# Pugsley.net
KiCad netlist of a schematic drawn in EAGLE
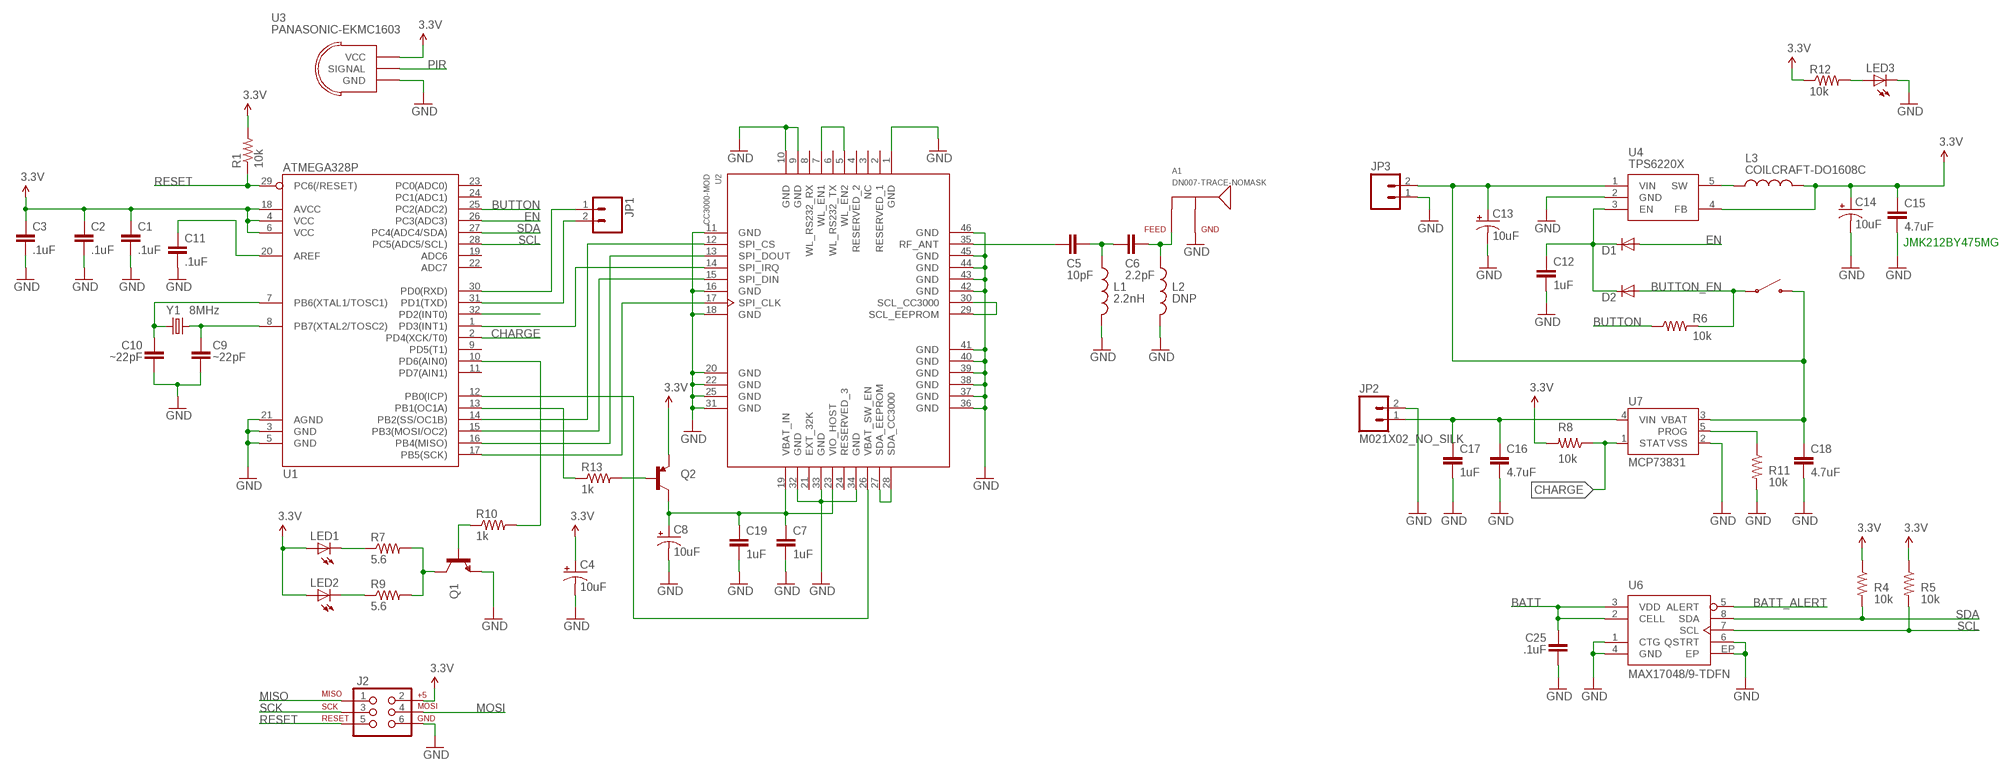
[diagram p0: schematic, sheet 1]

(export (version "E")
  (design (tool "Eeschema 10.0.6"))
  (components
    (comp (ref "A1")
      (value "DN007-TRACE-NOMASK")
      (footprint "eagle-import:DN007-TRACE-NOMASK")
      (libsource (lib "eagle-import") (part "DN007-TRACE-NOMASK"))
    )
    (comp (ref "C1")
      (value ".1uF")
      (footprint "eagle-import:0402-CAP")
      (libsource (lib "eagle-import") (part "CAP0402-CAP"))
    )
    (comp (ref "C2")
      (value ".1uF")
      (footprint "eagle-import:0402-CAP")
      (libsource (lib "eagle-import") (part "CAP0402-CAP"))
    )
    (comp (ref "C3")
      (value ".1uF")
      (footprint "eagle-import:0402-CAP")
      (libsource (lib "eagle-import") (part "CAP0402-CAP"))
    )
    (comp (ref "C4")
      (value "10uF")
      (footprint "eagle-import:EIA3216")
      (libsource (lib "eagle-import") (part "CAP_POL1206"))
    )
    (comp (ref "C5")
      (value "10pF")
      (footprint "eagle-import:0402-CAP")
      (libsource (lib "eagle-import") (part "CAP0402-CAP"))
    )
    (comp (ref "C6")
      (value "2.2pF")
      (footprint "eagle-import:0402-CAP")
      (libsource (lib "eagle-import") (part "CAP0402-CAP"))
    )
    (comp (ref "C7")
      (value "1uF")
      (footprint "eagle-import:0402-CAP")
      (libsource (lib "eagle-import") (part "CAP0402-CAP"))
    )
    (comp (ref "C8")
      (value "10uF")
      (footprint "eagle-import:EIA3216")
      (libsource (lib "eagle-import") (part "CAP_POL1206"))
    )
    (comp (ref "C9")
      (value "~22pF")
      (footprint "eagle-import:0402-CAP")
      (libsource (lib "eagle-import") (part "CAP0402-CAP"))
    )
    (comp (ref "C10")
      (value "~22pF")
      (footprint "eagle-import:0402-CAP")
      (libsource (lib "eagle-import") (part "CAP0402-CAP"))
    )
    (comp (ref "C11")
      (value ".1uF")
      (footprint "eagle-import:0402-CAP")
      (libsource (lib "eagle-import") (part "CAP0402-CAP"))
    )
    (comp (ref "C12")
      (value "1uF")
      (footprint "eagle-import:0402-CAP")
      (libsource (lib "eagle-import") (part "CAP0402-CAP"))
    )
    (comp (ref "C13")
      (value "10uF")
      (footprint "eagle-import:EIA3216")
      (libsource (lib "eagle-import") (part "CAP_POL1206"))
    )
    (comp (ref "C14")
      (value "10uF")
      (footprint "eagle-import:EIA3216")
      (libsource (lib "eagle-import") (part "CAP_POL1206"))
    )
    (comp (ref "C15")
      (value "4.7uF")
      (footprint "eagle-import:0805")
      (libsource (lib "eagle-import") (part "CAP0805"))
    )
    (comp (ref "C16")
      (value "4.7uF")
      (footprint "eagle-import:0805")
      (libsource (lib "eagle-import") (part "CAP0805"))
    )
    (comp (ref "C17")
      (value "1uF")
      (footprint "eagle-import:0402-CAP")
      (libsource (lib "eagle-import") (part "CAP0402-CAP"))
    )
    (comp (ref "C18")
      (value "4.7uF")
      (footprint "eagle-import:0805")
      (libsource (lib "eagle-import") (part "CAP0805"))
    )
    (comp (ref "C19")
      (value "1uF")
      (footprint "eagle-import:0402-CAP")
      (libsource (lib "eagle-import") (part "CAP0402-CAP"))
    )
    (comp (ref "C25")
      (value ".1uF")
      (footprint "eagle-import:0402-CAP")
      (libsource (lib "eagle-import") (part "CAP0402-CAP"))
    )
    (comp (ref "D1")
      (value "DIODESOD")
      (footprint "eagle-import:SOD-323")
      (libsource (lib "eagle-import") (part "DIODESOD"))
    )
    (comp (ref "D2")
      (value "DIODESOD")
      (footprint "eagle-import:SOD-323")
      (libsource (lib "eagle-import") (part "DIODESOD"))
    )
    (comp (ref "J2")
      (value "AVR_SPI_PRG_6NS")
      (footprint "eagle-import:2X3-NS")
      (libsource (lib "eagle-import") (part "AVR_SPI_PRG_6NS"))
    )
    (comp (ref "JP1")
      (value "M021X02_NO_SILK")
      (footprint "eagle-import:1X02_NO_SILK")
      (libsource (lib "eagle-import") (part "M021X02_NO_SILK"))
    )
    (comp (ref "JP2")
      (value "M021X02_NO_SILK")
      (footprint "eagle-import:1X02_NO_SILK")
      (libsource (lib "eagle-import") (part "M021X02_NO_SILK"))
    )
    (comp (ref "JP3")
      (value "M021X02_NO_SILK")
      (footprint "eagle-import:1X02_NO_SILK")
      (libsource (lib "eagle-import") (part "M021X02_NO_SILK"))
    )
    (comp (ref "L1")
      (value "2.2nH")
      (footprint "eagle-import:C0402")
      (libsource (lib "eagle-import") (part "INDUCTOR0402"))
    )
    (comp (ref "L2")
      (value "DNP")
      (footprint "eagle-import:C0402")
      (libsource (lib "eagle-import") (part "INDUCTOR0402"))
    )
    (comp (ref "L3")
      (value "COILCRAFT-DO1608C")
      (footprint "eagle-import:COILCRAFT-DO1608C")
      (libsource (lib "eagle-import") (part "COILCRAFT-DO1608C"))
    )
    (comp (ref "LED1")
      (value "LED0603")
      (footprint "eagle-import:LED-0603")
      (libsource (lib "eagle-import") (part "LED0603"))
    )
    (comp (ref "LED2")
      (value "LED0603")
      (footprint "eagle-import:LED-0603")
      (libsource (lib "eagle-import") (part "LED0603"))
    )
    (comp (ref "LED3")
      (value "LED0603")
      (footprint "eagle-import:LED-0603")
      (libsource (lib "eagle-import") (part "LED0603"))
    )
    (comp (ref "Q1")
      (value "TRANSISTOR_NPNSOT23")
      (footprint "eagle-import:SOT23")
      (libsource (lib "eagle-import") (part "TRANSISTOR_NPNSOT23"))
    )
    (comp (ref "Q2")
      (value "TRANSISTOR_PNPSMD")
      (footprint "eagle-import:SOT23-3")
      (libsource (lib "eagle-import") (part "TRANSISTOR_PNPSMD"))
    )
    (comp (ref "R1")
      (value "10k")
      (footprint "eagle-import:0402-RES")
      (libsource (lib "eagle-import") (part "RESISTOR0402-RES"))
    )
    (comp (ref "R4")
      (value "10k")
      (footprint "eagle-import:0402-RES")
      (libsource (lib "eagle-import") (part "RESISTOR0402-RES"))
    )
    (comp (ref "R5")
      (value "10k")
      (footprint "eagle-import:0402-RES")
      (libsource (lib "eagle-import") (part "RESISTOR0402-RES"))
    )
    (comp (ref "R6")
      (value "10k")
      (footprint "eagle-import:0402-RES")
      (libsource (lib "eagle-import") (part "RESISTOR0402-RES"))
    )
    (comp (ref "R7")
      (value "5.6")
      (footprint "eagle-import:0402-RES")
      (libsource (lib "eagle-import") (part "RESISTOR0402-RES"))
    )
    (comp (ref "R8")
      (value "10k")
      (footprint "eagle-import:0402-RES")
      (libsource (lib "eagle-import") (part "RESISTOR0402-RES"))
    )
    (comp (ref "R9")
      (value "5.6")
      (footprint "eagle-import:0402-RES")
      (libsource (lib "eagle-import") (part "RESISTOR0402-RES"))
    )
    (comp (ref "R10")
      (value "1k")
      (footprint "eagle-import:0402-RES")
      (libsource (lib "eagle-import") (part "RESISTOR0402-RES"))
    )
    (comp (ref "R11")
      (value "10k")
      (footprint "eagle-import:0402-RES")
      (libsource (lib "eagle-import") (part "RESISTOR0402-RES"))
    )
    (comp (ref "R12")
      (value "10k")
      (footprint "eagle-import:0402-RES")
      (libsource (lib "eagle-import") (part "RESISTOR0402-RES"))
    )
    (comp (ref "R13")
      (value "1k")
      (footprint "eagle-import:0402-RES")
      (libsource (lib "eagle-import") (part "RESISTOR0402-RES"))
    )
    (comp (ref "S1")
      (value "C&K-KSR2XX")
      (footprint "eagle-import:C&K-KSR2XX")
      (libsource (lib "eagle-import") (part "C&K-KSR2XX"))
    )
    (comp (ref "U1")
      (value "ATMEGA328P")
      (footprint "eagle-import:TQFP32-08")
      (libsource (lib "eagle-import") (part "ATMEGA328_SMT"))
    )
    (comp (ref "U2")
      (value "CC3000-MOD")
      (footprint "eagle-import:CC3000")
      (libsource (lib "eagle-import") (part "CC3000-MOD"))
    )
    (comp (ref "U3")
      (value "PANASONIC-EKMC1603")
      (footprint "eagle-import:PIR-PANASONIC-EKMC1603XXX")
      (libsource (lib "eagle-import") (part "PANASONIC-EKMC1603"))
    )
    (comp (ref "U4")
      (value "TPS6220X")
      (footprint "eagle-import:SOT23-5")
      (libsource (lib "eagle-import") (part "TPS6220X"))
    )
    (comp (ref "U6")
      (value "MAX17048/9-TDFN")
      (footprint "eagle-import:TDFN-8")
      (libsource (lib "eagle-import") (part "MAX17048/9-TDFN"))
    )
    (comp (ref "U7")
      (value "MCP73831")
      (footprint "eagle-import:SOT23-5")
      (libsource (lib "eagle-import") (part "MCP73831"))
    )
    (comp (ref "Y1")
      (value "8MHz")
      (footprint "eagle-import:CRYSTAL-SMD-5X3")
      (libsource (lib "eagle-import") (part "CRYSTAL5X3"))
    )
  )
  (nets
    (net (code "1") (name "/BATT") (class "Default")
      (node (ref "C13") (pin "A") (pinfunction "+_A") (pintype "passive"))
      (node (ref "C18") (pin "1") (pinfunction "1_1") (pintype "passive"))
      (node (ref "C25") (pin "1") (pinfunction "1_1") (pintype "passive"))
      (node (ref "JP3") (pin "2") (pinfunction "2_2") (pintype "passive"))
      (node (ref "S1") (pin "P$2") (pinfunction "2_P$2") (pintype "bidirectional"))
      (node (ref "U4") (pin "1") (pinfunction "VIN_1") (pintype "power_in"))
      (node (ref "U6") (pin "2") (pinfunction "CELL_2") (pintype "input"))
      (node (ref "U6") (pin "3") (pinfunction "VDD_3") (pintype "power_in"))
      (node (ref "U7") (pin "3") (pinfunction "VBAT_3") (pintype "power_in"))
    )
    (net (code "2") (name "/BATT_ALERT") (class "Default")
      (node (ref "U6") (pin "5") (pinfunction "ALERT_5") (pintype "open_collector"))
    )
    (net (code "3") (name "/BUTTON") (class "Default")
      (node (ref "R6") (pin "1") (pinfunction "1_1") (pintype "passive"))
      (node (ref "U1") (pin "25") (pinfunction "PC2(ADC2)_25") (pintype "bidirectional"))
    )
    (net (code "4") (name "/BUTTON_EN") (class "Default")
      (node (ref "D2") (pin "2") (pinfunction "A_2") (pintype "passive"))
      (node (ref "R6") (pin "2") (pinfunction "2_2") (pintype "passive"))
      (node (ref "S1") (pin "P$1") (pinfunction "1_P$1") (pintype "bidirectional"))
    )
    (net (code "5") (name "/EN") (class "Default")
      (node (ref "D1") (pin "2") (pinfunction "A_2") (pintype "passive"))
      (node (ref "U1") (pin "26") (pinfunction "PC3(ADC3)_26") (pintype "bidirectional"))
    )
    (net (code "6") (name "/MISO") (class "Default")
      (node (ref "J2") (pin "1") (pinfunction "1_1") (pintype "passive"))
      (node (ref "U1") (pin "16") (pinfunction "PB4(MISO)_16") (pintype "bidirectional"))
      (node (ref "U2") (pin "13") (pinfunction "SPI_DOUT_13") (pintype "output"))
    )
    (net (code "7") (name "/MOSI") (class "Default")
      (node (ref "J2") (pin "4") (pinfunction "4_4") (pintype "passive"))
      (node (ref "U1") (pin "15") (pinfunction "PB3(MOSI/OC2)_15") (pintype "bidirectional"))
      (node (ref "U2") (pin "15") (pinfunction "SPI_DIN_15") (pintype "input"))
    )
    (net (code "8") (name "/PIR") (class "Default")
      (node (ref "U1") (pin "32") (pinfunction "PD2(INT0)_32") (pintype "bidirectional"))
      (node (ref "U3") (pin "OUT") (pinfunction "SIGNAL_OUT") (pintype "output"))
    )
    (net (code "9") (name "/RESET") (class "Default")
      (node (ref "J2") (pin "5") (pinfunction "5_5") (pintype "passive"))
      (node (ref "R1") (pin "1") (pinfunction "1_1") (pintype "passive"))
      (node (ref "U1") (pin "29") (pinfunction "PC6(/RESET)_29") (pintype "bidirectional"))
    )
    (net (code "10") (name "/SCK") (class "Default")
      (node (ref "J2") (pin "3") (pinfunction "3_3") (pintype "passive"))
      (node (ref "U1") (pin "17") (pinfunction "PB5(SCK)_17") (pintype "bidirectional"))
      (node (ref "U2") (pin "17") (pinfunction "SPI_CLK_17") (pintype "input"))
    )
    (net (code "11") (name "/SCL") (class "Default")
      (node (ref "R5") (pin "2") (pinfunction "2_2") (pintype "passive"))
      (node (ref "U1") (pin "28") (pinfunction "PC5(ADC5/SCL)_28") (pintype "bidirectional"))
      (node (ref "U6") (pin "7") (pinfunction "SCL_7") (pintype "input"))
    )
    (net (code "12") (name "/SDA") (class "Default")
      (node (ref "R4") (pin "2") (pinfunction "2_2") (pintype "passive"))
      (node (ref "U1") (pin "27") (pinfunction "PC4(ADC4/SDA)_27") (pintype "bidirectional"))
      (node (ref "U6") (pin "8") (pinfunction "SDA_8") (pintype "bidirectional"))
    )
    (net (code "13") (name "3.3V") (class "Default")
      (node (ref "C1") (pin "1") (pinfunction "1_1") (pintype "passive"))
      (node (ref "C14") (pin "A") (pinfunction "+_A") (pintype "passive"))
      (node (ref "C15") (pin "1") (pinfunction "1_1") (pintype "passive"))
      (node (ref "C2") (pin "1") (pinfunction "1_1") (pintype "passive"))
      (node (ref "C3") (pin "1") (pinfunction "1_1") (pintype "passive"))
      (node (ref "C4") (pin "A") (pinfunction "+_A") (pintype "passive"))
      (node (ref "J2") (pin "2") (pinfunction "2_2") (pintype "passive"))
      (node (ref "L3") (pin "2") (pinfunction "2_2") (pintype "passive"))
      (node (ref "LED1") (pin "A") (pinfunction "A_A") (pintype "passive"))
      (node (ref "LED2") (pin "A") (pinfunction "A_A") (pintype "passive"))
      (node (ref "Q2") (pin "2") (pinfunction "E_2") (pintype "passive"))
      (node (ref "R1") (pin "2") (pinfunction "2_2") (pintype "passive"))
      (node (ref "R12") (pin "1") (pinfunction "1_1") (pintype "passive"))
      (node (ref "R4") (pin "1") (pinfunction "1_1") (pintype "passive"))
      (node (ref "R5") (pin "1") (pinfunction "1_1") (pintype "passive"))
      (node (ref "R8") (pin "2") (pinfunction "2_2") (pintype "passive"))
      (node (ref "U1") (pin "18") (pinfunction "AVCC_18") (pintype "bidirectional"))
      (node (ref "U1") (pin "4") (pinfunction "VCC_4") (pintype "bidirectional"))
      (node (ref "U1") (pin "6") (pinfunction "VCC_6") (pintype "bidirectional"))
      (node (ref "U3") (pin "VDD") (pinfunction "VCC_VDD") (pintype "power_in"))
      (node (ref "U4") (pin "4") (pinfunction "FB_4") (pintype "input"))
    )
    (net (code "14") (name "CHARGE") (class "Default")
      (node (ref "R8") (pin "1") (pinfunction "1_1") (pintype "passive"))
      (node (ref "U1") (pin "2") (pinfunction "PD4(XCK/T0)_2") (pintype "bidirectional"))
      (node (ref "U7") (pin "1") (pinfunction "STAT_1") (pintype "output"))
    )
    (net (code "15") (name "GND") (class "Default")
      (node (ref "A1") (pin "GND@1") (pinfunction "GND_GND@1") (pintype "input"))
      (node (ref "A1") (pin "GND@2") (pinfunction "GND_GND@2") (pintype "input"))
      (node (ref "C1") (pin "2") (pinfunction "2_2") (pintype "passive"))
      (node (ref "C10") (pin "2") (pinfunction "2_2") (pintype "passive"))
      (node (ref "C11") (pin "2") (pinfunction "2_2") (pintype "passive"))
      (node (ref "C12") (pin "2") (pinfunction "2_2") (pintype "passive"))
      (node (ref "C13") (pin "C") (pinfunction "-_C") (pintype "passive"))
      (node (ref "C14") (pin "C") (pinfunction "-_C") (pintype "passive"))
      (node (ref "C15") (pin "2") (pinfunction "2_2") (pintype "passive"))
      (node (ref "C16") (pin "2") (pinfunction "2_2") (pintype "passive"))
      (node (ref "C17") (pin "2") (pinfunction "2_2") (pintype "passive"))
      (node (ref "C18") (pin "2") (pinfunction "2_2") (pintype "passive"))
      (node (ref "C19") (pin "2") (pinfunction "2_2") (pintype "passive"))
      (node (ref "C2") (pin "2") (pinfunction "2_2") (pintype "passive"))
      (node (ref "C25") (pin "2") (pinfunction "2_2") (pintype "passive"))
      (node (ref "C3") (pin "2") (pinfunction "2_2") (pintype "passive"))
      (node (ref "C4") (pin "C") (pinfunction "-_C") (pintype "passive"))
      (node (ref "C7") (pin "2") (pinfunction "2_2") (pintype "passive"))
      (node (ref "C8") (pin "C") (pinfunction "-_C") (pintype "passive"))
      (node (ref "C9") (pin "2") (pinfunction "2_2") (pintype "passive"))
      (node (ref "J2") (pin "6") (pinfunction "6_6") (pintype "passive"))
      (node (ref "JP2") (pin "2") (pinfunction "2_2") (pintype "passive"))
      (node (ref "JP3") (pin "1") (pinfunction "1_1") (pintype "passive"))
      (node (ref "L1") (pin "2") (pinfunction "2_2") (pintype "passive"))
      (node (ref "L2") (pin "2") (pinfunction "2_2") (pintype "passive"))
      (node (ref "LED3") (pin "C") (pinfunction "C_C") (pintype "passive"))
      (node (ref "Q1") (pin "2") (pinfunction "E_2") (pintype "passive"))
      (node (ref "R11") (pin "2") (pinfunction "2_2") (pintype "passive"))
      (node (ref "U1") (pin "21") (pinfunction "AGND_21") (pintype "bidirectional"))
      (node (ref "U1") (pin "3") (pinfunction "GND_3") (pintype "bidirectional"))
      (node (ref "U1") (pin "5") (pinfunction "GND_5") (pintype "bidirectional"))
      (node (ref "U2") (pin "1") (pinfunction "GND_1") (pintype "power_in"))
      (node (ref "U2") (pin "10") (pinfunction "GND_10") (pintype "power_in"))
      (node (ref "U2") (pin "11") (pinfunction "GND_11") (pintype "power_in"))
      (node (ref "U2") (pin "16") (pinfunction "GND_16") (pintype "power_in"))
      (node (ref "U2") (pin "18") (pinfunction "GND_18") (pintype "power_in"))
      (node (ref "U2") (pin "20") (pinfunction "GND_20") (pintype "power_in"))
      (node (ref "U2") (pin "22") (pinfunction "GND_22") (pintype "power_in"))
      (node (ref "U2") (pin "25") (pinfunction "GND_25") (pintype "power_in"))
      (node (ref "U2") (pin "31") (pinfunction "GND_31") (pintype "power_in"))
      (node (ref "U2") (pin "32") (pinfunction "GND_32") (pintype "power_in"))
      (node (ref "U2") (pin "33") (pinfunction "GND_33") (pintype "power_in"))
      (node (ref "U2") (pin "34") (pinfunction "GND_34") (pintype "power_in"))
      (node (ref "U2") (pin "36") (pinfunction "GND_36") (pintype "power_in"))
      (node (ref "U2") (pin "37") (pinfunction "GND_37") (pintype "power_in"))
      (node (ref "U2") (pin "38") (pinfunction "GND_38") (pintype "power_in"))
      (node (ref "U2") (pin "39") (pinfunction "GND_39") (pintype "power_in"))
      (node (ref "U2") (pin "40") (pinfunction "GND_40") (pintype "power_in"))
      (node (ref "U2") (pin "41") (pinfunction "GND_41") (pintype "power_in"))
      (node (ref "U2") (pin "42") (pinfunction "GND_42") (pintype "power_in"))
      (node (ref "U2") (pin "43") (pinfunction "GND_43") (pintype "power_in"))
      (node (ref "U2") (pin "44") (pinfunction "GND_44") (pintype "power_in"))
      (node (ref "U2") (pin "45") (pinfunction "GND_45") (pintype "power_in"))
      (node (ref "U2") (pin "46") (pinfunction "GND_46") (pintype "power_in"))
      (node (ref "U2") (pin "9") (pinfunction "GND_9") (pintype "power_in"))
      (node (ref "U3") (pin "GND") (pinfunction "GND_GND") (pintype "power_in"))
      (node (ref "U4") (pin "2") (pinfunction "GND_2") (pintype "power_in"))
      (node (ref "U6") (pin "1") (pinfunction "CTG_1") (pintype "power_in"))
      (node (ref "U6") (pin "4") (pinfunction "GND_4") (pintype "power_in"))
      (node (ref "U6") (pin "6") (pinfunction "QSTRT_6") (pintype "input"))
      (node (ref "U6") (pin "EP") (pinfunction "EP_EP") (pintype "power_in"))
      (node (ref "U7") (pin "2") (pinfunction "VSS_2") (pintype "power_in"))
    )
    (net (code "16") (name "Net-(A1-PadFEED)") (class "Default")
      (node (ref "A1") (pin "FEED") (pinfunction "FEED_FEED") (pintype "power_in"))
      (node (ref "C6") (pin "1") (pinfunction "1_1") (pintype "passive"))
      (node (ref "L2") (pin "1") (pinfunction "1_1") (pintype "passive"))
    )
    (net (code "17") (name "Net-(C5-Pad1)") (class "Default")
      (node (ref "C5") (pin "1") (pinfunction "1_1") (pintype "passive"))
      (node (ref "C6") (pin "2") (pinfunction "2_2") (pintype "passive"))
      (node (ref "L1") (pin "1") (pinfunction "1_1") (pintype "passive"))
    )
    (net (code "18") (name "Net-(C8-+)") (class "Default")
      (node (ref "C19") (pin "1") (pinfunction "1_1") (pintype "passive"))
      (node (ref "C7") (pin "1") (pinfunction "1_1") (pintype "passive"))
      (node (ref "C8") (pin "A") (pinfunction "+_A") (pintype "passive"))
      (node (ref "Q2") (pin "3") (pinfunction "C_3") (pintype "passive"))
      (node (ref "U2") (pin "19") (pinfunction "VBAT_IN_19") (pintype "power_in"))
      (node (ref "U2") (pin "23") (pinfunction "VIO_HOST_23") (pintype "power_in"))
    )
    (net (code "19") (name "Net-(D1-C)") (class "Default")
      (node (ref "C12") (pin "1") (pinfunction "1_1") (pintype "passive"))
      (node (ref "D1") (pin "1") (pinfunction "C_1") (pintype "passive"))
      (node (ref "D2") (pin "1") (pinfunction "C_1") (pintype "passive"))
      (node (ref "U4") (pin "3") (pinfunction "EN_3") (pintype "input"))
    )
    (net (code "20") (name "Net-(LED1-PadC)") (class "Default")
      (node (ref "LED1") (pin "C") (pinfunction "C_C") (pintype "passive"))
      (node (ref "R7") (pin "1") (pinfunction "1_1") (pintype "passive"))
    )
    (net (code "21") (name "Net-(LED2-PadC)") (class "Default")
      (node (ref "LED2") (pin "C") (pinfunction "C_C") (pintype "passive"))
      (node (ref "R9") (pin "1") (pinfunction "1_1") (pintype "passive"))
    )
    (net (code "22") (name "Net-(LED3-PadA)") (class "Default")
      (node (ref "LED3") (pin "A") (pinfunction "A_A") (pintype "passive"))
      (node (ref "R12") (pin "2") (pinfunction "2_2") (pintype "passive"))
    )
    (net (code "23") (name "Net-(Q1-B)") (class "Default")
      (node (ref "Q1") (pin "1") (pinfunction "B_1") (pintype "passive"))
      (node (ref "R10") (pin "1") (pinfunction "1_1") (pintype "passive"))
    )
    (net (code "24") (name "Net-(Q1-C)") (class "Default")
      (node (ref "Q1") (pin "3") (pinfunction "C_3") (pintype "passive"))
      (node (ref "R7") (pin "2") (pinfunction "2_2") (pintype "passive"))
      (node (ref "R9") (pin "2") (pinfunction "2_2") (pintype "passive"))
    )
    (net (code "25") (name "Net-(Q2-B)") (class "Default")
      (node (ref "Q2") (pin "1") (pinfunction "B_1") (pintype "passive"))
      (node (ref "R13") (pin "2") (pinfunction "2_2") (pintype "passive"))
    )
    (net (code "26") (name "Net-(U1-AREF)") (class "Default")
      (node (ref "C11") (pin "1") (pinfunction "1_1") (pintype "passive"))
      (node (ref "U1") (pin "20") (pinfunction "AREF_20") (pintype "bidirectional"))
    )
    (net (code "27") (name "Net-(U1-PB0(ICP))") (class "Default")
      (node (ref "U1") (pin "12") (pinfunction "PB0(ICP)_12") (pintype "bidirectional"))
      (node (ref "U2") (pin "26") (pinfunction "VBAT_SW_EN_26") (pintype "input"))
    )
    (net (code "28") (name "Net-(U1-PB1(OC1A))") (class "Default")
      (node (ref "R13") (pin "1") (pinfunction "1_1") (pintype "passive"))
      (node (ref "U1") (pin "13") (pinfunction "PB1(OC1A)_13") (pintype "bidirectional"))
    )
    (net (code "29") (name "Net-(U1-PB2(SS{slash}OC1B))") (class "Default")
      (node (ref "U1") (pin "14") (pinfunction "PB2(SS/OC1B)_14") (pintype "bidirectional"))
      (node (ref "U2") (pin "12") (pinfunction "SPI_CS_12") (pintype "input"))
    )
    (net (code "30") (name "Net-(U1-PB6(XTAL1{slash}TOSC1))") (class "Default")
      (node (ref "C10") (pin "1") (pinfunction "1_1") (pintype "passive"))
      (node (ref "U1") (pin "7") (pinfunction "PB6(XTAL1/TOSC1)_7") (pintype "bidirectional"))
      (node (ref "Y1") (pin "1") (pinfunction "1_1") (pintype "passive"))
    )
    (net (code "31") (name "Net-(U1-PB7(XTAL2{slash}TOSC2))") (class "Default")
      (node (ref "C9") (pin "1") (pinfunction "1_1") (pintype "passive"))
      (node (ref "U1") (pin "8") (pinfunction "PB7(XTAL2/TOSC2)_8") (pintype "bidirectional"))
      (node (ref "Y1") (pin "3") (pinfunction "2_3") (pintype "passive"))
    )
    (net (code "32") (name "Net-(U1-PD0(RXD))") (class "Default")
      (node (ref "JP1") (pin "1") (pinfunction "1_1") (pintype "passive"))
      (node (ref "U1") (pin "30") (pinfunction "PD0(RXD)_30") (pintype "bidirectional"))
    )
    (net (code "33") (name "Net-(U1-PD1(TXD))") (class "Default")
      (node (ref "JP1") (pin "2") (pinfunction "2_2") (pintype "passive"))
      (node (ref "U1") (pin "31") (pinfunction "PD1(TXD)_31") (pintype "bidirectional"))
    )
    (net (code "34") (name "Net-(U1-PD3(INT1))") (class "Default")
      (node (ref "U1") (pin "1") (pinfunction "PD3(INT1)_1") (pintype "bidirectional"))
      (node (ref "U2") (pin "14") (pinfunction "SPI_IRQ_14") (pintype "output"))
    )
    (net (code "35") (name "Net-(U1-PD6(AIN0))") (class "Default")
      (node (ref "R10") (pin "2") (pinfunction "2_2") (pintype "passive"))
      (node (ref "U1") (pin "10") (pinfunction "PD6(AIN0)_10") (pintype "bidirectional"))
    )
    (net (code "36") (name "Net-(U2-RF_ANT)") (class "Default")
      (node (ref "C5") (pin "2") (pinfunction "2_2") (pintype "passive"))
      (node (ref "U2") (pin "35") (pinfunction "RF_ANT_35") (pintype "bidirectional"))
    )
    (net (code "37") (name "Net-(U2-SCL_CC3000)") (class "Default")
      (node (ref "U2") (pin "29") (pinfunction "SCL_EEPROM_29") (pintype "bidirectional"))
      (node (ref "U2") (pin "30") (pinfunction "SCL_CC3000_30") (pintype "bidirectional"))
    )
    (net (code "38") (name "Net-(U2-SDA_CC3000)") (class "Default")
      (node (ref "U2") (pin "27") (pinfunction "SDA_EEPROM_27") (pintype "bidirectional"))
      (node (ref "U2") (pin "28") (pinfunction "SDA_CC3000_28") (pintype "bidirectional"))
    )
    (net (code "39") (name "Net-(U2-WL_EN1)") (class "Default")
      (node (ref "U2") (pin "5") (pinfunction "WL_EN2_5") (pintype "input"))
      (node (ref "U2") (pin "7") (pinfunction "WL_EN1_7") (pintype "input"))
    )
    (net (code "40") (name "Net-(U4-SW)") (class "Default")
      (node (ref "L3") (pin "1") (pinfunction "1_1") (pintype "passive"))
      (node (ref "U4") (pin "5") (pinfunction "SW_5") (pintype "bidirectional"))
    )
    (net (code "41") (name "Net-(U7-PROG)") (class "Default")
      (node (ref "R11") (pin "1") (pinfunction "1_1") (pintype "passive"))
      (node (ref "U7") (pin "5") (pinfunction "PROG_5") (pintype "input"))
    )
    (net (code "42") (name "Net-(U7-VIN)") (class "Default")
      (node (ref "C16") (pin "1") (pinfunction "1_1") (pintype "passive"))
      (node (ref "C17") (pin "1") (pinfunction "1_1") (pintype "passive"))
      (node (ref "JP2") (pin "1") (pinfunction "1_1") (pintype "passive"))
      (node (ref "U7") (pin "4") (pinfunction "VIN_4") (pintype "power_in"))
    )
    (net (code "43") (name "unconnected-(U1-ADC6-Pad19)") (class "Default")
      (node (ref "U1") (pin "19") (pinfunction "ADC6_19") (pintype "bidirectional"))
    )
    (net (code "44") (name "unconnected-(U1-ADC7-Pad22)") (class "Default")
      (node (ref "U1") (pin "22") (pinfunction "ADC7_22") (pintype "bidirectional"))
    )
    (net (code "45") (name "unconnected-(U1-PC0(ADC0)-Pad23)") (class "Default")
      (node (ref "U1") (pin "23") (pinfunction "PC0(ADC0)_23") (pintype "bidirectional"))
    )
    (net (code "46") (name "unconnected-(U1-PC1(ADC1)-Pad24)") (class "Default")
      (node (ref "U1") (pin "24") (pinfunction "PC1(ADC1)_24") (pintype "bidirectional"))
    )
    (net (code "47") (name "unconnected-(U1-PD5(T1)-Pad9)") (class "Default")
      (node (ref "U1") (pin "9") (pinfunction "PD5(T1)_9") (pintype "bidirectional"))
    )
    (net (code "48") (name "unconnected-(U1-PD7(AIN1)-Pad11)") (class "Default")
      (node (ref "U1") (pin "11") (pinfunction "PD7(AIN1)_11") (pintype "bidirectional"))
    )
    (net (code "49") (name "unconnected-(U2-EXT_32K-Pad21)") (class "Default")
      (node (ref "U2") (pin "21") (pinfunction "EXT_32K_21") (pintype "bidirectional"))
    )
    (net (code "50") (name "unconnected-(U2-NC-Pad3)") (class "Default")
      (node (ref "U2") (pin "3") (pinfunction "NC_3") (pintype "no_connect"))
    )
    (net (code "51") (name "unconnected-(U2-RESERVED_1-Pad2)") (class "Default")
      (node (ref "U2") (pin "2") (pinfunction "RESERVED_1_2") (pintype "bidirectional"))
    )
    (net (code "52") (name "unconnected-(U2-RESERVED_2-Pad4)") (class "Default")
      (node (ref "U2") (pin "4") (pinfunction "RESERVED_2_4") (pintype "bidirectional"))
    )
    (net (code "53") (name "unconnected-(U2-RESERVED_3-Pad24)") (class "Default")
      (node (ref "U2") (pin "24") (pinfunction "RESERVED_3_24") (pintype "bidirectional"))
    )
    (net (code "54") (name "unconnected-(U2-WL_RS232_RX-Pad8)") (class "Default")
      (node (ref "U2") (pin "8") (pinfunction "WL_RS232_RX_8") (pintype "input"))
    )
    (net (code "55") (name "unconnected-(U2-WL_RS232_TX-Pad6)") (class "Default")
      (node (ref "U2") (pin "6") (pinfunction "WL_RS232_TX_6") (pintype "output"))
    )
  )
)
